# Sheet_handling_module.net
KiCad netlist of a schematic drawn in Altium Designer
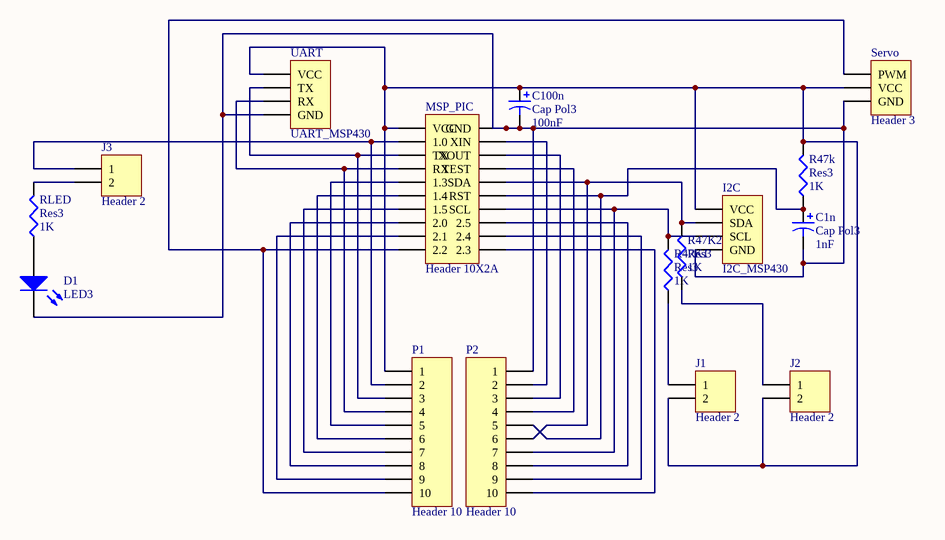
[diagram p0: Sheet_handling_module.SchDoc]

(export (version "E")
  (design (tool "Eeschema 10.0.6"))
  (components
    (comp (ref "C1n")
      (value "Cap Pol3")
      (footprint "C0805")
      (description "Polarized Capacitor (Surface Mount)")
      (fields (field (name "ALTIUM_VALUE") "1nF") (field (name "PUBLISHER") "Altium Limited"))
      (libsource (lib "Miscellaneous Devices") (part "Cap Pol3"))
    )
    (comp (ref "C100n")
      (value "Cap Pol3")
      (footprint "C0805")
      (description "Polarized Capacitor (Surface Mount)")
      (fields (field (name "ALTIUM_VALUE") "100nF") (field (name "PUBLISHER") "Altium Limited"))
      (libsource (lib "Miscellaneous Devices") (part "Cap Pol3"))
    )
    (comp (ref "D1")
      (value "LED3")
      (footprint "6-0805_L")
      (description "Typical BLUE SiC LED")
      (fields (field (name "PUBLISHER") "Altium Limited"))
      (libsource (lib "Miscellaneous Devices") (part "LED3"))
    )
    (comp (ref "I2C")
      (value "I2C_MSP430")
      (footprint "HDR1X4")
      (description "Header, 4-Pin")
      (fields (field (name "PUBLISHER") "Altium Limited"))
      (libsource (lib "Miscellaneous Connectors") (part "Header 4"))
    )
    (comp (ref "J1")
      (value "Header 2")
      (footprint "HDR1X2")
      (description "Header, 2-Pin")
      (fields (field (name "PUBLISHER") "Altium Limited"))
      (libsource (lib "Miscellaneous Connectors") (part "Header 2"))
    )
    (comp (ref "J2")
      (value "Header 2")
      (footprint "HDR1X2")
      (description "Header, 2-Pin")
      (fields (field (name "PUBLISHER") "Altium Limited"))
      (libsource (lib "Miscellaneous Connectors") (part "Header 2"))
    )
    (comp (ref "J3")
      (value "Header 2")
      (footprint "HDR1X2")
      (description "Header, 2-Pin")
      (fields (field (name "PUBLISHER") "Altium Limited"))
      (libsource (lib "Miscellaneous Connectors") (part "Header 2"))
    )
    (comp (ref "MSP_PIC")
      (value "Header 10X2A")
      (footprint "N020")
      (description "Header, 10-Pin, Dual row")
      (fields (field (name "PUBLISHER") "Altium Limited"))
      (libsource (lib "Miscellaneous Connectors") (part "Header 10X2A"))
    )
    (comp (ref "P1")
      (value "Header 10")
      (footprint "HDR1X10")
      (description "Header, 10-Pin")
      (fields (field (name "PUBLISHER") "Altium Limited"))
      (libsource (lib "Miscellaneous Connectors") (part "Header 10"))
    )
    (comp (ref "P2")
      (value "Header 10")
      (footprint "HDR1X10")
      (description "Header, 10-Pin")
      (fields (field (name "PUBLISHER") "Altium Limited"))
      (libsource (lib "") (part "Header 10_1"))
    )
    (comp (ref "R47k")
      (value "Res3")
      (footprint "INDC3216")
      (description "Resistor")
      (fields (field (name "ALTIUM_VALUE") "1K") (field (name "PUBLISHER") "Altium Limited"))
      (libsource (lib "Miscellaneous Devices") (part "Res3"))
    )
    (comp (ref "R47K1")
      (value "Res3")
      (footprint "INDC3216")
      (description "Resistor")
      (fields (field (name "ALTIUM_VALUE") "1K") (field (name "PUBLISHER") "Altium Limited"))
      (libsource (lib "Miscellaneous Devices") (part "Res3"))
    )
    (comp (ref "R47K2")
      (value "Res3")
      (footprint "INDC3216")
      (description "Resistor")
      (fields (field (name "ALTIUM_VALUE") "1K") (field (name "PUBLISHER") "Altium Limited"))
      (libsource (lib "Miscellaneous Devices") (part "Res3"))
    )
    (comp (ref "RLED")
      (value "Res3")
      (footprint "INDC3216")
      (description "Resistor")
      (fields (field (name "ALTIUM_VALUE") "1K") (field (name "PUBLISHER") "Altium Limited"))
      (libsource (lib "Miscellaneous Devices") (part "Res3"))
    )
    (comp (ref "Servo")
      (value "Header 3")
      (footprint "HDR1X3")
      (description "Header, 3-Pin")
      (fields (field (name "PUBLISHER") "Altium Limited"))
      (libsource (lib "Miscellaneous Connectors") (part "Header 3"))
    )
    (comp (ref "UART")
      (value "UART_MSP430")
      (footprint "HDR1X4")
      (description "Header, 4-Pin")
      (fields (field (name "PUBLISHER") "Altium Limited"))
      (libsource (lib "Miscellaneous Connectors") (part "Header 4"))
    )
  )
  (nets
    (net (code "1") (name "Net-(D1-A)") (class "Default")
      (node (ref "D1") (pin "1") (pinfunction "A_1") (pintype "passive"))
      (node (ref "RLED") (pin "1") (pinfunction "1_1") (pintype "passive"))
    )
    (net (code "2") (name "Net-(D1-K)") (class "Default")
      (node (ref "C100n") (pin "2") (pinfunction "2_2") (pintype "passive"))
      (node (ref "C1n") (pin "2") (pinfunction "2_2") (pintype "passive"))
      (node (ref "D1") (pin "2") (pinfunction "K_2") (pintype "passive"))
      (node (ref "I2C") (pin "1") (pinfunction "GND_1") (pintype "passive"))
      (node (ref "MSP_PIC") (pin "20") (pinfunction "GND_20") (pintype "passive"))
      (node (ref "P2") (pin "1") (pinfunction "1_1") (pintype "passive"))
      (node (ref "Servo") (pin "3") (pinfunction "GND_3") (pintype "passive"))
      (node (ref "UART") (pin "1") (pinfunction "GND_1") (pintype "passive"))
    )
    (net (code "3") (name "Net-(I2C-RX)") (class "Default")
      (node (ref "I2C") (pin "3") (pinfunction "RX_3") (pintype "passive"))
      (node (ref "MSP_PIC") (pin "14") (pinfunction "SCL_14") (pintype "passive"))
      (node (ref "P2") (pin "7") (pinfunction "7_7") (pintype "passive"))
      (node (ref "R47K1") (pin "2") (pinfunction "2_2") (pintype "passive"))
    )
    (net (code "4") (name "Net-(I2C-TX)") (class "Default")
      (node (ref "I2C") (pin "2") (pinfunction "TX_2") (pintype "passive"))
      (node (ref "MSP_PIC") (pin "15") (pinfunction "SDA_15") (pintype "passive"))
      (node (ref "P2") (pin "6") (pinfunction "6_6") (pintype "passive"))
      (node (ref "R47K2") (pin "2") (pinfunction "2_2") (pintype "passive"))
    )
    (net (code "5") (name "Net-(I2C-VCC)") (class "Default")
      (node (ref "C100n") (pin "1") (pinfunction "1_1") (pintype "passive"))
      (node (ref "I2C") (pin "4") (pinfunction "VCC_4") (pintype "passive"))
      (node (ref "J1") (pin "2") (pinfunction "2_2") (pintype "passive"))
      (node (ref "J2") (pin "2") (pinfunction "2_2") (pintype "passive"))
      (node (ref "MSP_PIC") (pin "1") (pinfunction "VCC_1") (pintype "passive"))
      (node (ref "P1") (pin "1") (pinfunction "1_1") (pintype "passive"))
      (node (ref "R47k") (pin "2") (pinfunction "2_2") (pintype "passive"))
      (node (ref "Servo") (pin "2") (pinfunction "VCC_2") (pintype "passive"))
      (node (ref "UART") (pin "4") (pinfunction "VCC_4") (pintype "passive"))
    )
    (net (code "6") (name "Net-(J1-Pad1)") (class "Default")
      (node (ref "J1") (pin "1") (pinfunction "1_1") (pintype "passive"))
      (node (ref "R47K1") (pin "1") (pinfunction "1_1") (pintype "passive"))
    )
    (net (code "7") (name "Net-(J2-Pad1)") (class "Default")
      (node (ref "J2") (pin "1") (pinfunction "1_1") (pintype "passive"))
      (node (ref "R47K2") (pin "1") (pinfunction "1_1") (pintype "passive"))
    )
    (net (code "8") (name "Net-(J3-Pad2)") (class "Default")
      (node (ref "J3") (pin "2") (pinfunction "2_2") (pintype "passive"))
      (node (ref "RLED") (pin "2") (pinfunction "2_2") (pintype "passive"))
    )
    (net (code "9") (name "Net-(MSP_PIC-1.0)") (class "Default")
      (node (ref "J3") (pin "1") (pinfunction "1_1") (pintype "passive"))
      (node (ref "MSP_PIC") (pin "2") (pinfunction "1.0_2") (pintype "passive"))
      (node (ref "P1") (pin "2") (pinfunction "2_2") (pintype "passive"))
    )
    (net (code "10") (name "Net-(MSP_PIC-1.3)") (class "Default")
      (node (ref "MSP_PIC") (pin "5") (pinfunction "1.3_5") (pintype "passive"))
      (node (ref "P1") (pin "5") (pinfunction "5_5") (pintype "passive"))
    )
    (net (code "11") (name "Net-(MSP_PIC-1.4)") (class "Default")
      (node (ref "MSP_PIC") (pin "6") (pinfunction "1.4_6") (pintype "passive"))
      (node (ref "P1") (pin "6") (pinfunction "6_6") (pintype "passive"))
    )
    (net (code "12") (name "Net-(MSP_PIC-1.5)") (class "Default")
      (node (ref "MSP_PIC") (pin "7") (pinfunction "1.5_7") (pintype "passive"))
      (node (ref "P1") (pin "7") (pinfunction "7_7") (pintype "passive"))
    )
    (net (code "13") (name "Net-(MSP_PIC-2.0)") (class "Default")
      (node (ref "MSP_PIC") (pin "8") (pinfunction "2.0_8") (pintype "passive"))
      (node (ref "P1") (pin "8") (pinfunction "8_8") (pintype "passive"))
    )
    (net (code "14") (name "Net-(MSP_PIC-2.1)") (class "Default")
      (node (ref "MSP_PIC") (pin "9") (pinfunction "2.1_9") (pintype "passive"))
      (node (ref "P1") (pin "9") (pinfunction "9_9") (pintype "passive"))
    )
    (net (code "15") (name "Net-(MSP_PIC-2.2)") (class "Default")
      (node (ref "MSP_PIC") (pin "10") (pinfunction "2.2_10") (pintype "passive"))
      (node (ref "P1") (pin "10") (pinfunction "10_10") (pintype "passive"))
      (node (ref "Servo") (pin "1") (pinfunction "PWM_1") (pintype "passive"))
    )
    (net (code "16") (name "Net-(MSP_PIC-2.3)") (class "Default")
      (node (ref "MSP_PIC") (pin "11") (pinfunction "2.3_11") (pintype "passive"))
      (node (ref "P2") (pin "10") (pinfunction "10_10") (pintype "passive"))
    )
    (net (code "17") (name "Net-(MSP_PIC-2.4)") (class "Default")
      (node (ref "MSP_PIC") (pin "12") (pinfunction "2.4_12") (pintype "passive"))
      (node (ref "P2") (pin "9") (pinfunction "9_9") (pintype "passive"))
    )
    (net (code "18") (name "Net-(MSP_PIC-2.5)") (class "Default")
      (node (ref "MSP_PIC") (pin "13") (pinfunction "2.5_13") (pintype "passive"))
      (node (ref "P2") (pin "8") (pinfunction "8_8") (pintype "passive"))
    )
    (net (code "19") (name "Net-(MSP_PIC-RST)") (class "Default")
      (node (ref "C1n") (pin "1") (pinfunction "1_1") (pintype "passive"))
      (node (ref "MSP_PIC") (pin "16") (pinfunction "RST_16") (pintype "passive"))
      (node (ref "P2") (pin "5") (pinfunction "5_5") (pintype "passive"))
      (node (ref "R47k") (pin "1") (pinfunction "1_1") (pintype "passive"))
    )
    (net (code "20") (name "Net-(MSP_PIC-RX)") (class "Default")
      (node (ref "MSP_PIC") (pin "4") (pinfunction "RX_4") (pintype "passive"))
      (node (ref "P1") (pin "4") (pinfunction "4_4") (pintype "passive"))
      (node (ref "UART") (pin "3") (pinfunction "RX_3") (pintype "passive"))
    )
    (net (code "21") (name "Net-(MSP_PIC-TEST)") (class "Default")
      (node (ref "MSP_PIC") (pin "17") (pinfunction "TEST_17") (pintype "passive"))
      (node (ref "P2") (pin "4") (pinfunction "4_4") (pintype "passive"))
    )
    (net (code "22") (name "Net-(MSP_PIC-TX)") (class "Default")
      (node (ref "MSP_PIC") (pin "3") (pinfunction "TX_3") (pintype "passive"))
      (node (ref "P1") (pin "3") (pinfunction "3_3") (pintype "passive"))
      (node (ref "UART") (pin "2") (pinfunction "TX_2") (pintype "passive"))
    )
    (net (code "23") (name "Net-(MSP_PIC-XIN)") (class "Default")
      (node (ref "MSP_PIC") (pin "19") (pinfunction "XIN_19") (pintype "passive"))
      (node (ref "P2") (pin "2") (pinfunction "2_2") (pintype "passive"))
    )
    (net (code "24") (name "Net-(MSP_PIC-XOUT)") (class "Default")
      (node (ref "MSP_PIC") (pin "18") (pinfunction "XOUT_18") (pintype "passive"))
      (node (ref "P2") (pin "3") (pinfunction "3_3") (pintype "passive"))
    )
  )
)
